# MainBoard_V100_BLR.net
KiCad netlist of a schematic drawn in Altium Designer
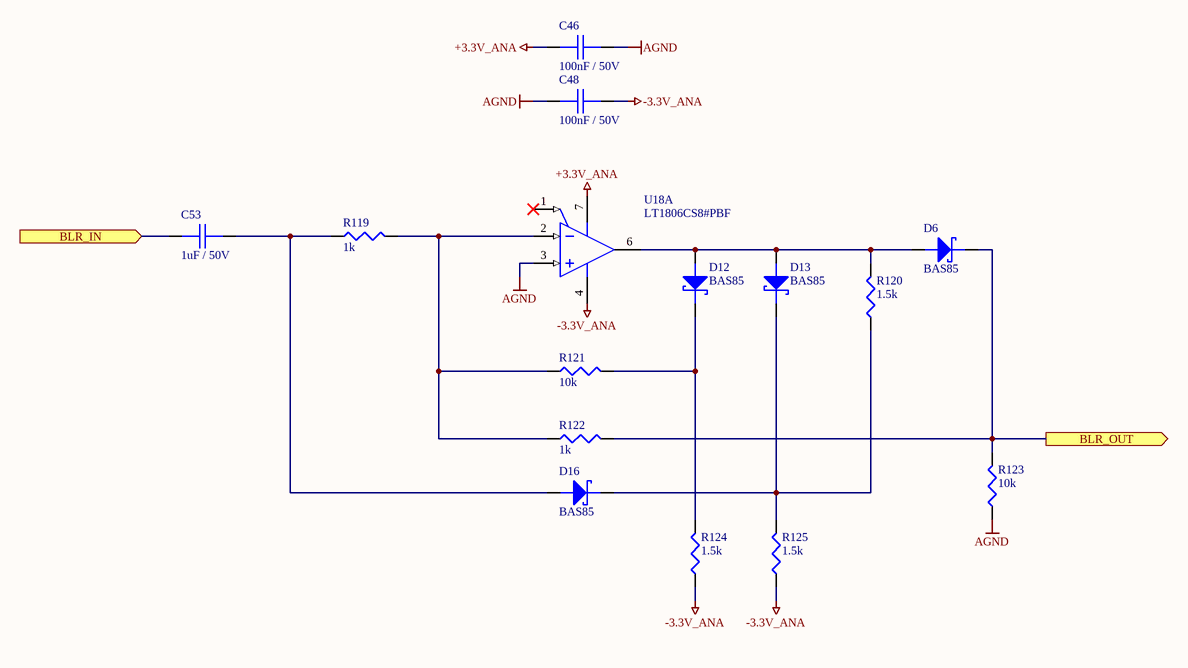
[diagram p0: MainBoard_V100_BLR.SchDoc]

(export (version "E")
  (design (tool "Eeschema 10.0.6"))
  (components
    (comp (ref "C46")
      (value "100nF / 50V")
      (footprint "0805_C")
      (description "100nF 50V X7R")
      (fields (field (name "PART NUMBER") "SMD0805-100nF-50V"))
      (libsource (lib "ALTIUM_DB_LIB") (part "CAP_NONPOL"))
    )
    (comp (ref "C48")
      (value "100nF / 50V")
      (footprint "0805_C")
      (description "100nF 50V X7R")
      (fields (field (name "PART NUMBER") "SMD0805-100nF-50V"))
      (libsource (lib "ALTIUM_DB_LIB") (part "CAP_NONPOL"))
    )
    (comp (ref "C53")
      (value "1uF / 50V")
      (footprint "0805_C")
      (description "1uF 50V X7R")
      (fields (field (name "PART NUMBER") "SMD0805-1uF-50V"))
      (libsource (lib "ALTIUM_DB_LIB") (part "CAP_NONPOL"))
    )
    (comp (ref "D6")
      (value "BAS85")
      (footprint "SOD80")
      (description "Small Signal Schottky Diode, Single, 30 V, 200 mA,  125 °C")
      (libsource (lib "ALTIUM_DB_LIB") (part "DIODE_SCHOTTKY"))
    )
    (comp (ref "D12")
      (value "BAS85")
      (footprint "SOD80")
      (description "Small Signal Schottky Diode, Single, 30 V, 200 mA,  125 °C")
      (libsource (lib "ALTIUM_DB_LIB") (part "DIODE_SCHOTTKY"))
    )
    (comp (ref "D13")
      (value "BAS85")
      (footprint "SOD80")
      (description "Small Signal Schottky Diode, Single, 30 V, 200 mA,  125 °C")
      (libsource (lib "ALTIUM_DB_LIB") (part "DIODE_SCHOTTKY"))
    )
    (comp (ref "D16")
      (value "BAS85")
      (footprint "SOD80")
      (description "Small Signal Schottky Diode, Single, 30 V, 200 mA,  125 °C")
      (libsource (lib "ALTIUM_DB_LIB") (part "DIODE_SCHOTTKY"))
    )
    (comp (ref "R119")
      (value "1k")
      (footprint "0805")
      (description "1k 0805 0.125W 1%")
      (fields (field (name "PART NUMBER") "SMD0805-1k 1%"))
      (libsource (lib "ALTIUM_DB_LIB") (part "RESISTOR"))
    )
    (comp (ref "R120")
      (value "1.5k")
      (footprint "0805")
      (description "1.5k 0805 0.125W 1%")
      (fields (field (name "PART NUMBER") "SMD0805-1.5k-1%"))
      (libsource (lib "ALTIUM_DB_LIB") (part "RESISTOR"))
    )
    (comp (ref "R121")
      (value "10k")
      (footprint "0805")
      (description "10k 0805 0.125W 1%")
      (fields (field (name "PART NUMBER") "SMD0805-10k 1%"))
      (libsource (lib "ALTIUM_DB_LIB") (part "RESISTOR"))
    )
    (comp (ref "R122")
      (value "1k")
      (footprint "0805")
      (description "1k 0805 0.125W 1%")
      (fields (field (name "PART NUMBER") "SMD0805-1k 1%"))
      (libsource (lib "ALTIUM_DB_LIB") (part "RESISTOR"))
    )
    (comp (ref "R123")
      (value "10k")
      (footprint "0805")
      (description "10k 0805 0.125W 1%")
      (fields (field (name "PART NUMBER") "SMD0805-10k 1%"))
      (libsource (lib "ALTIUM_DB_LIB") (part "RESISTOR"))
    )
    (comp (ref "R124")
      (value "1.5k")
      (footprint "0805")
      (description "1.5k 0805 0.125W 1%")
      (fields (field (name "PART NUMBER") "SMD0805-1.5k-1%"))
      (libsource (lib "ALTIUM_DB_LIB") (part "RESISTOR"))
    )
    (comp (ref "R125")
      (value "1.5k")
      (footprint "0805")
      (description "1.5k 0805 0.125W 1%")
      (fields (field (name "PART NUMBER") "SMD0805-1.5k-1%"))
      (libsource (lib "ALTIUM_DB_LIB") (part "RESISTOR"))
    )
    (comp (ref "U18")
      (value "LT1806CS8#PBF")
      (footprint "SO-8")
      (fields
        (field (name "MANUFACTURER") "Linear Technology")
        (field (name "LINEAR TECHNOLOGY PART NUMBER") "LT1806")
      )
      (libsource (lib "ALTIUM_DB_LIB") (part "LT1806CS8#PBF"))
    )
  )
  (nets
    (net (code "1") (name "+3.3V_ANA") (class "Default")
      (node (ref "C46") (pin "1") (pintype "passive"))
      (node (ref "U18") (pin "7") (pinfunction "V+_7") (pintype "power_in"))
    )
    (net (code "2") (name "-3.3V_ANA") (class "Default")
      (node (ref "C48") (pin "2") (pintype "passive"))
      (node (ref "R124") (pin "1") (pintype "passive"))
      (node (ref "R125") (pin "1") (pintype "passive"))
      (node (ref "U18") (pin "4") (pinfunction "V-_4") (pintype "power_in"))
    )
    (net (code "3") (name "/BLR_IN") (class "Default") (node (ref "C53") (pin "1") (pintype "passive")))
    (net (code "4") (name "/BLR_OUT") (class "Default")
      (node (ref "D6") (pin "K") (pinfunction "K_K") (pintype "passive"))
      (node (ref "R122") (pin "2") (pintype "passive"))
      (node (ref "R123") (pin "2") (pintype "passive"))
    )
    (net (code "5") (name "AGND") (class "Default")
      (node (ref "C46") (pin "2") (pintype "passive"))
      (node (ref "C48") (pin "1") (pintype "passive"))
      (node (ref "R123") (pin "1") (pintype "passive"))
      (node (ref "U18") (pin "3") (pinfunction "+IN_3") (pintype "input"))
    )
    (net (code "6") (name "Net-(C53-Pad2)") (class "Default")
      (node (ref "C53") (pin "2") (pintype "passive"))
      (node (ref "D16") (pin "A") (pinfunction "A_A") (pintype "passive"))
      (node (ref "R119") (pin "1") (pintype "passive"))
    )
    (net (code "7") (name "Net-(D12-PadK)") (class "Default")
      (node (ref "D12") (pin "K") (pinfunction "K_K") (pintype "passive"))
      (node (ref "R121") (pin "2") (pintype "passive"))
      (node (ref "R124") (pin "2") (pintype "passive"))
    )
    (net (code "8") (name "Net-(D13-PadK)") (class "Default")
      (node (ref "D13") (pin "K") (pinfunction "K_K") (pintype "passive"))
      (node (ref "D16") (pin "K") (pinfunction "K_K") (pintype "passive"))
      (node (ref "R120") (pin "1") (pintype "passive"))
      (node (ref "R125") (pin "2") (pintype "passive"))
    )
    (net (code "9") (name "Net-(U18A--IN)") (class "Default")
      (node (ref "R119") (pin "2") (pintype "passive"))
      (node (ref "R121") (pin "1") (pintype "passive"))
      (node (ref "R122") (pin "1") (pintype "passive"))
      (node (ref "U18") (pin "2") (pinfunction "-IN_2") (pintype "input"))
    )
    (net (code "10") (name "Net-(U18A-OUT)") (class "Default")
      (node (ref "D12") (pin "A") (pinfunction "A_A") (pintype "passive"))
      (node (ref "D13") (pin "A") (pinfunction "A_A") (pintype "passive"))
      (node (ref "D6") (pin "A") (pinfunction "A_A") (pintype "passive"))
      (node (ref "R120") (pin "2") (pintype "passive"))
      (node (ref "U18") (pin "6") (pinfunction "OUT_6") (pintype "tri_state"))
    )
    (net (code "11") (name "unconnected-(U18A-~{SHDN}-Pad1)") (class "Default")
      (node (ref "U18") (pin "1") (pinfunction "~{SHDN}_1") (pintype "input+no_connect"))
    )
  )
)
